# schematic.net
KiCad netlist of a schematic drawn in EAGLE
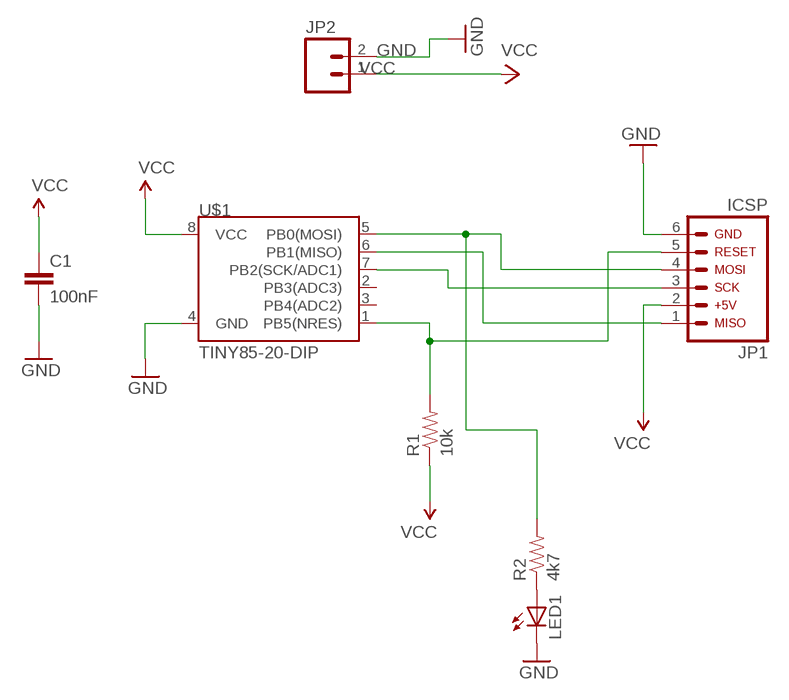
[diagram p0: schematic, sheet 1]

(export (version "E")
  (design (tool "Eeschema 10.0.6"))
  (components
    (comp (ref "C1")
      (value "100nF")
      (footprint "eagle-import:CAP-PTH-SMALL-KIT")
      (libsource (lib "eagle-import") (part "0.1UF-50V-20%(PTH)KIT-EZ"))
    )
    (comp (ref "JP1")
      (value "ARDUINO_CONN-ICSP")
      (footprint "eagle-import:CONN-2X03")
      (libsource (lib "eagle-import") (part "ARDUINO_CONN-ICSP"))
    )
    (comp (ref "JP2")
      (value "M02LOCK")
      (footprint "eagle-import:1X02_LOCK")
      (libsource (lib "eagle-import") (part "M02LOCK"))
    )
    (comp (ref "LED1")
      (value "LED5MM")
      (footprint "eagle-import:LED5MM")
      (libsource (lib "eagle-import") (part "LED5MM"))
    )
    (comp (ref "R1")
      (value "10k")
      (footprint "eagle-import:1_6W-RES")
      (libsource (lib "eagle-import") (part "RESISTORPTH-1/6W"))
    )
    (comp (ref "R2")
      (value "4k7")
      (footprint "eagle-import:1_6W-RES")
      (libsource (lib "eagle-import") (part "RESISTORPTH-1/6W"))
    )
    (comp (ref "U$1")
      (value "TINY85-20-DIP")
      (footprint "eagle-import:DIP08")
      (libsource (lib "eagle-import") (part "ATTINY45TINY85-20-DIP"))
    )
  )
  (nets
    (net (code "1") (name "GND") (class "Default")
      (node (ref "C1") (pin "2") (pinfunction "2_2") (pintype "passive"))
      (node (ref "JP1") (pin "6") (pinfunction "6_6") (pintype "passive"))
      (node (ref "JP2") (pin "2") (pinfunction "2_2") (pintype "passive"))
      (node (ref "LED1") (pin "K") (pinfunction "C_K") (pintype "passive"))
      (node (ref "U$1") (pin "4") (pinfunction "GND_4") (pintype "bidirectional"))
    )
    (net (code "2") (name "Net-(LED1-PadA)") (class "Default")
      (node (ref "LED1") (pin "A") (pinfunction "A_A") (pintype "passive"))
      (node (ref "R2") (pin "1") (pinfunction "1_1") (pintype "passive"))
    )
    (net (code "3") (name "Net-(U$1-PB0(MOSI))") (class "Default")
      (node (ref "JP1") (pin "4") (pinfunction "4_4") (pintype "passive"))
      (node (ref "R2") (pin "2") (pinfunction "2_2") (pintype "passive"))
      (node (ref "U$1") (pin "5") (pinfunction "PB0(MOSI)_5") (pintype "bidirectional"))
    )
    (net (code "4") (name "Net-(U$1-PB1(MISO))") (class "Default")
      (node (ref "JP1") (pin "1") (pinfunction "1_1") (pintype "passive"))
      (node (ref "U$1") (pin "6") (pinfunction "PB1(MISO)_6") (pintype "bidirectional"))
    )
    (net (code "5") (name "Net-(U$1-PB2(SCK{slash}ADC1))") (class "Default")
      (node (ref "JP1") (pin "3") (pinfunction "3_3") (pintype "passive"))
      (node (ref "U$1") (pin "7") (pinfunction "PB2(SCK/ADC1)_7") (pintype "bidirectional"))
    )
    (net (code "6") (name "Net-(U$1-PB5(NRES))") (class "Default")
      (node (ref "JP1") (pin "5") (pinfunction "5_5") (pintype "passive"))
      (node (ref "R1") (pin "2") (pinfunction "2_2") (pintype "passive"))
      (node (ref "U$1") (pin "1") (pinfunction "PB5(NRES)_1") (pintype "bidirectional"))
    )
    (net (code "7") (name "VCC") (class "Default")
      (node (ref "C1") (pin "1") (pinfunction "1_1") (pintype "passive"))
      (node (ref "JP1") (pin "2") (pinfunction "2_2") (pintype "passive"))
      (node (ref "JP2") (pin "1") (pinfunction "1_1") (pintype "passive"))
      (node (ref "R1") (pin "1") (pinfunction "1_1") (pintype "passive"))
      (node (ref "U$1") (pin "8") (pinfunction "VCC_8") (pintype "bidirectional"))
    )
    (net (code "8") (name "unconnected-(U$1-PB3(ADC3)-Pad2)") (class "Default")
      (node (ref "U$1") (pin "2") (pinfunction "PB3(ADC3)_2") (pintype "bidirectional"))
    )
    (net (code "9") (name "unconnected-(U$1-PB4(ADC2)-Pad3)") (class "Default")
      (node (ref "U$1") (pin "3") (pinfunction "PB4(ADC2)_3") (pintype "bidirectional"))
    )
  )
)
